# AB_ESP8266.net
KiCad netlist of a schematic drawn in EAGLE
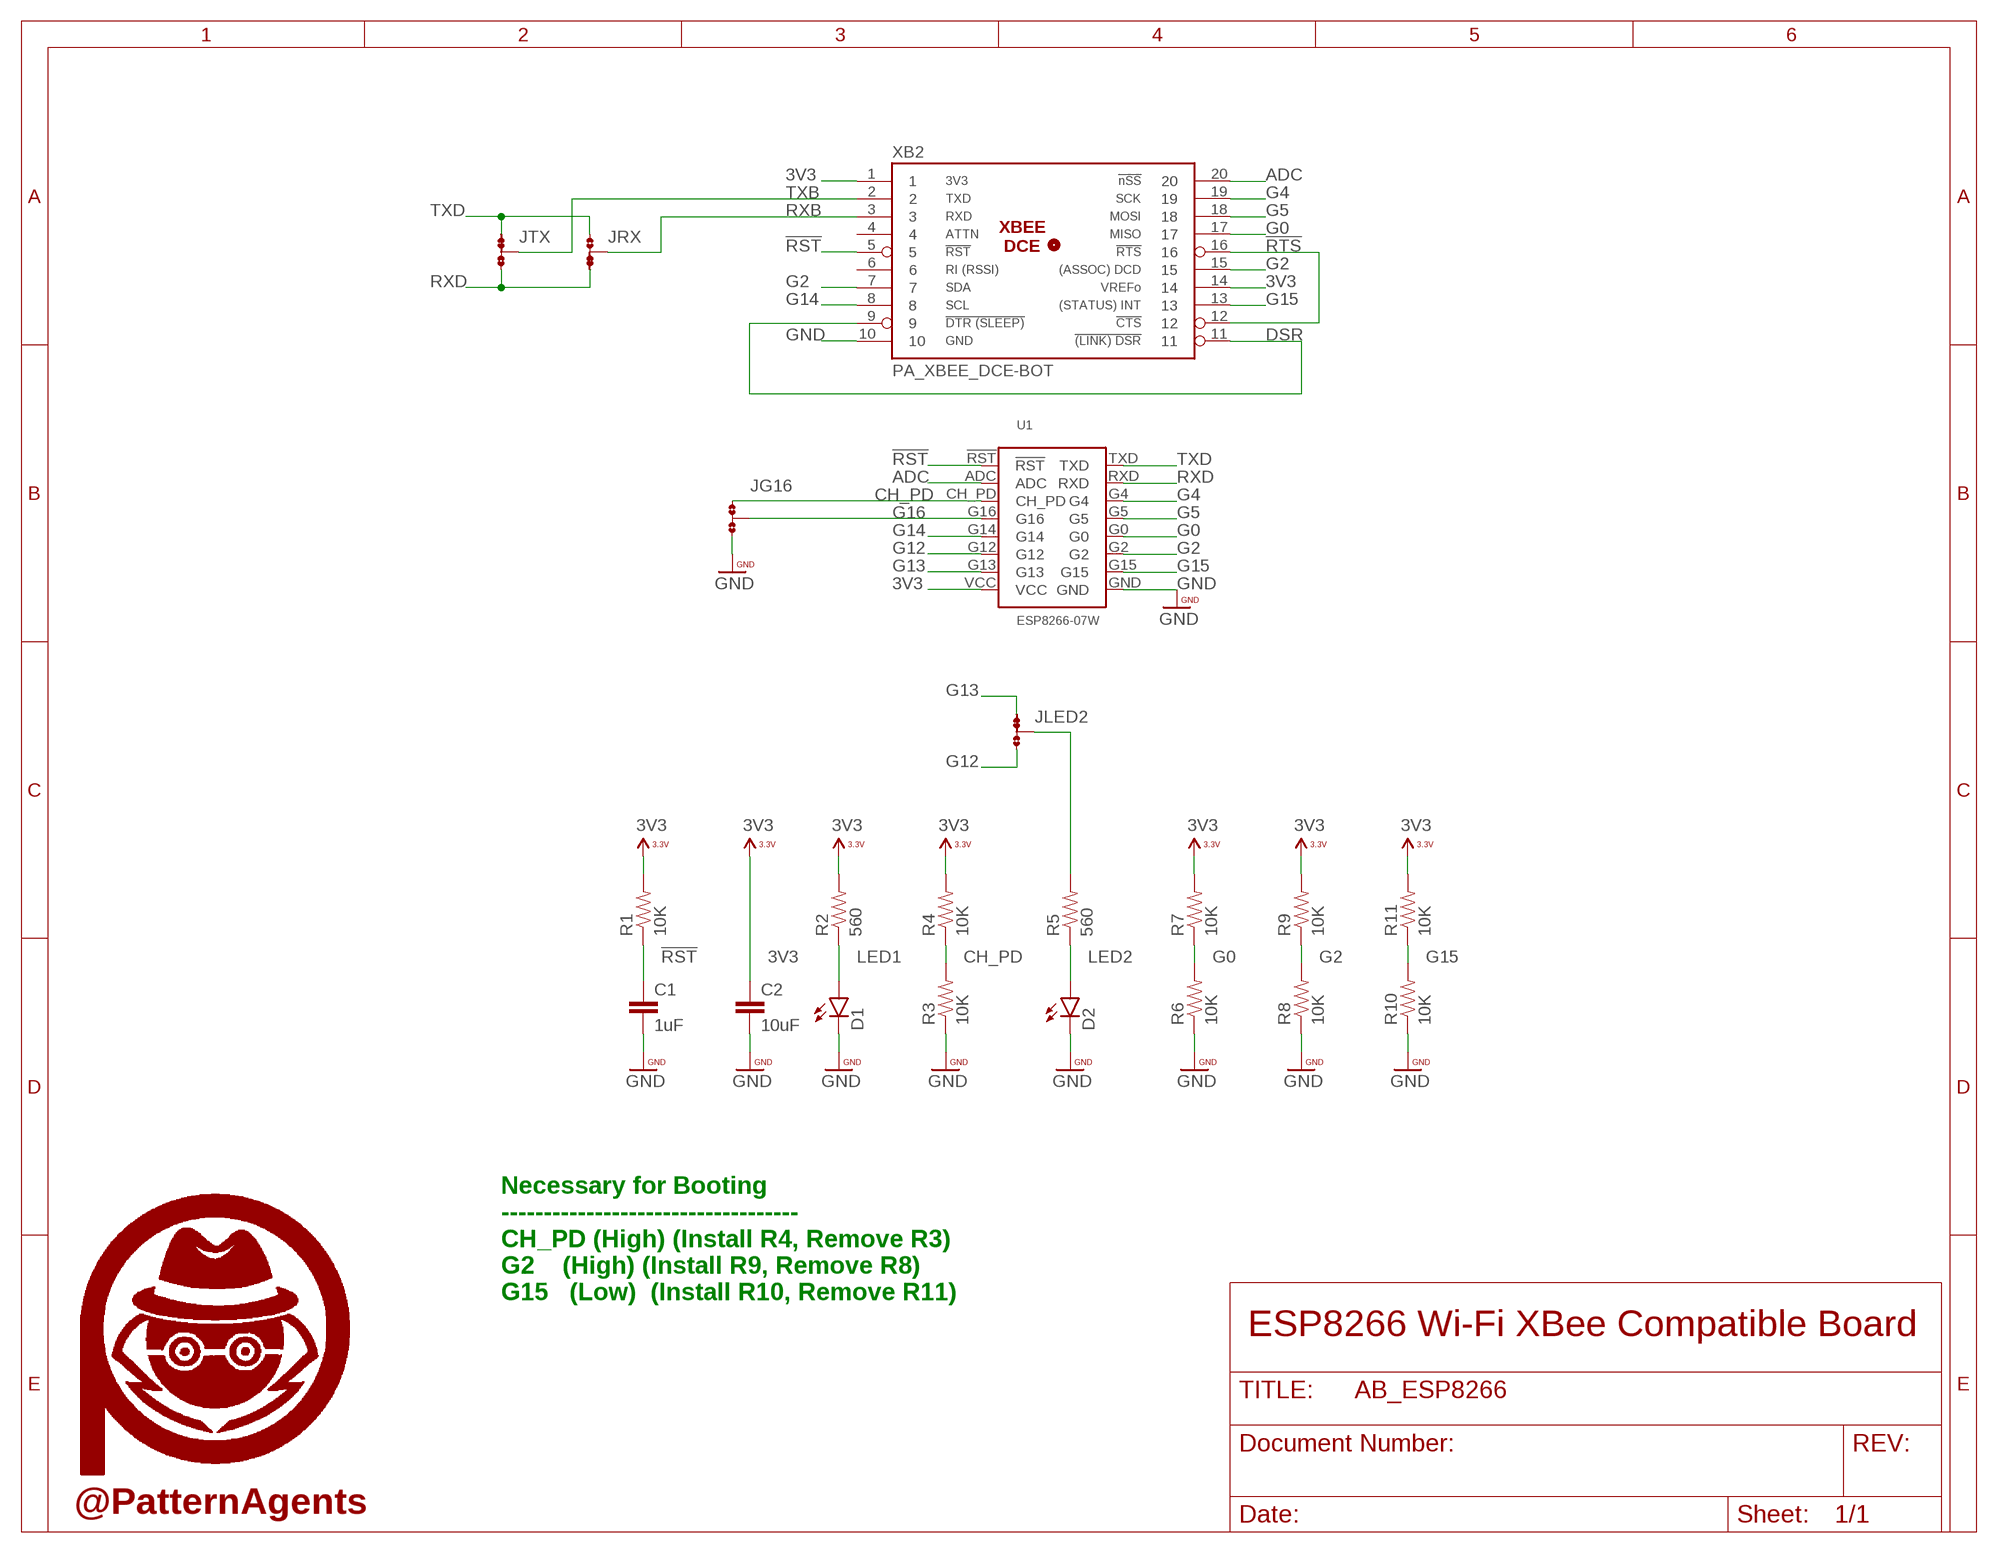
[diagram p0: schematic, sheet 1]

(export (version "E")
  (design (tool "Eeschema 10.0.6"))
  (components
    (comp (ref "C1")
      (value "1uF")
      (footprint "eagle-import:0603-CAP")
      (libsource (lib "eagle-import") (part "CAP0603-CAP"))
    )
    (comp (ref "C2")
      (value "10uF")
      (footprint "eagle-import:0603-CAP")
      (libsource (lib "eagle-import") (part "CAP0603-CAP"))
    )
    (comp (ref "D1")
      (value "LED0603")
      (footprint "eagle-import:LED-0603")
      (libsource (lib "eagle-import") (part "LED0603"))
    )
    (comp (ref "D2")
      (value "LED0603")
      (footprint "eagle-import:LED-0603")
      (libsource (lib "eagle-import") (part "LED0603"))
    )
    (comp (ref "JG16")
      (value "JMP-3-NO")
      (footprint "eagle-import:JMP-3-NO")
      (libsource (lib "eagle-import") (part "JMP-3-NO"))
    )
    (comp (ref "JLED2")
      (value "JMP-3-1_2")
      (footprint "eagle-import:JMP-3-1_2")
      (libsource (lib "eagle-import") (part "JMP-3-1_2"))
    )
    (comp (ref "JRX")
      (value "JMP-3-2_3")
      (footprint "eagle-import:JMP-3-2_3")
      (libsource (lib "eagle-import") (part "JMP-3-2_3"))
    )
    (comp (ref "JTX")
      (value "JMP-3-1_2")
      (footprint "eagle-import:JMP-3-1_2")
      (libsource (lib "eagle-import") (part "JMP-3-1_2"))
    )
    (comp (ref "R1")
      (value "10K")
      (footprint "eagle-import:0603-RES")
      (libsource (lib "eagle-import") (part "RESISTOR_SFE0603-RES"))
    )
    (comp (ref "R2")
      (value "560")
      (footprint "eagle-import:0603-RES")
      (libsource (lib "eagle-import") (part "RESISTOR_SFE0603-RES"))
    )
    (comp (ref "R3")
      (value "10K")
      (footprint "eagle-import:0603-RES")
      (libsource (lib "eagle-import") (part "RESISTOR_SFE0603-RES"))
    )
    (comp (ref "R4")
      (value "10K")
      (footprint "eagle-import:0603-RES")
      (libsource (lib "eagle-import") (part "RESISTOR_SFE0603-RES"))
    )
    (comp (ref "R5")
      (value "560")
      (footprint "eagle-import:0603-RES")
      (libsource (lib "eagle-import") (part "RESISTOR_SFE0603-RES"))
    )
    (comp (ref "R6")
      (value "10K")
      (footprint "eagle-import:0603-RES")
      (libsource (lib "eagle-import") (part "RESISTOR_SFE0603-RES"))
    )
    (comp (ref "R7")
      (value "10K")
      (footprint "eagle-import:0603-RES")
      (libsource (lib "eagle-import") (part "RESISTOR_SFE0603-RES"))
    )
    (comp (ref "R8")
      (value "10K")
      (footprint "eagle-import:0603-RES")
      (libsource (lib "eagle-import") (part "RESISTOR_SFE0603-RES"))
    )
    (comp (ref "R9")
      (value "10K")
      (footprint "eagle-import:0603-RES")
      (libsource (lib "eagle-import") (part "RESISTOR_SFE0603-RES"))
    )
    (comp (ref "R10")
      (value "10K")
      (footprint "eagle-import:0603-RES")
      (libsource (lib "eagle-import") (part "RESISTOR_SFE0603-RES"))
    )
    (comp (ref "R11")
      (value "10K")
      (footprint "eagle-import:0603-RES")
      (libsource (lib "eagle-import") (part "RESISTOR_SFE0603-RES"))
    )
    (comp (ref "U$18")
      (value "PA_LOGO_SYMSMALL")
      (footprint "eagle-import:PA_LOGO_AGENT_SMALL_SYM")
      (libsource (lib "eagle-import") (part "PA_LOGO_SYMSMALL"))
    )
    (comp (ref "U$19")
      (value "PA_LOGO_SYMSMALL")
      (footprint "eagle-import:PA_LOGO_AGENT_SMALL_SYM")
      (libsource (lib "eagle-import") (part "PA_LOGO_SYMSMALL"))
    )
    (comp (ref "U1")
      (value "ESP8266-07W")
      (footprint "eagle-import:ESP8266-07W")
      (libsource (lib "eagle-import") (part "ESP8266-07W"))
    )
    (comp (ref "XB2")
      (value "PA_XBEE_DCE-BOT")
      (footprint "eagle-import:PA_XBEE_SMD_BOT")
      (libsource (lib "eagle-import") (part "PA_XBEE_DCE-BOT"))
    )
  )
  (nets
    (net (code "1") (name "/ADC") (class "Default")
      (node (ref "U1") (pin "ADC") (pinfunction "ADC_ADC") (pintype "bidirectional"))
      (node (ref "XB2") (pin "20") (pinfunction "20_20") (pintype "input"))
    )
    (net (code "2") (name "/CH_PD") (class "Default")
      (node (ref "JG16") (pin "1") (pinfunction "1_1") (pintype "passive"))
      (node (ref "R3") (pin "2") (pinfunction "2_2") (pintype "passive"))
      (node (ref "R4") (pin "1") (pinfunction "1_1") (pintype "passive"))
      (node (ref "U1") (pin "CH_PD") (pinfunction "CH_PD_CH_PD") (pintype "bidirectional"))
    )
    (net (code "3") (name "/DSR") (class "Default")
      (node (ref "XB2") (pin "11") (pinfunction "11_11") (pintype "output"))
      (node (ref "XB2") (pin "9") (pinfunction "9_9") (pintype "input"))
    )
    (net (code "4") (name "/G0") (class "Default")
      (node (ref "R6") (pin "2") (pinfunction "2_2") (pintype "passive"))
      (node (ref "R7") (pin "1") (pinfunction "1_1") (pintype "passive"))
      (node (ref "U1") (pin "G0") (pinfunction "G0_G0") (pintype "bidirectional"))
      (node (ref "XB2") (pin "17") (pinfunction "17_17") (pintype "output"))
    )
    (net (code "5") (name "/G2") (class "Default")
      (node (ref "R8") (pin "2") (pinfunction "2_2") (pintype "passive"))
      (node (ref "R9") (pin "1") (pinfunction "1_1") (pintype "passive"))
      (node (ref "U1") (pin "G2") (pinfunction "G2_G2") (pintype "bidirectional"))
      (node (ref "XB2") (pin "15") (pinfunction "15_15") (pintype "output"))
      (node (ref "XB2") (pin "7") (pinfunction "7_7") (pintype "bidirectional"))
    )
    (net (code "6") (name "/G4") (class "Default")
      (node (ref "U1") (pin "G4") (pinfunction "G4_G4") (pintype "bidirectional"))
      (node (ref "XB2") (pin "19") (pinfunction "19_19") (pintype "input"))
    )
    (net (code "7") (name "/G5") (class "Default")
      (node (ref "U1") (pin "G5") (pinfunction "G5_G5") (pintype "bidirectional"))
      (node (ref "XB2") (pin "18") (pinfunction "18_18") (pintype "input"))
    )
    (net (code "8") (name "/G12") (class "Default")
      (node (ref "JLED2") (pin "3") (pinfunction "3_3") (pintype "passive"))
      (node (ref "U1") (pin "G12") (pinfunction "G12_G12") (pintype "bidirectional"))
    )
    (net (code "9") (name "/G13") (class "Default")
      (node (ref "JLED2") (pin "1") (pinfunction "1_1") (pintype "passive"))
      (node (ref "U1") (pin "G13") (pinfunction "G13_G13") (pintype "bidirectional"))
    )
    (net (code "10") (name "/G14") (class "Default")
      (node (ref "U1") (pin "G14") (pinfunction "G14_G14") (pintype "bidirectional"))
      (node (ref "XB2") (pin "8") (pinfunction "8_8") (pintype "bidirectional"))
    )
    (net (code "11") (name "/G15") (class "Default")
      (node (ref "R10") (pin "2") (pinfunction "2_2") (pintype "passive"))
      (node (ref "R11") (pin "1") (pinfunction "1_1") (pintype "passive"))
      (node (ref "U1") (pin "G15") (pinfunction "G15_G15") (pintype "bidirectional"))
      (node (ref "XB2") (pin "13") (pinfunction "13_13") (pintype "output"))
    )
    (net (code "12") (name "/G16") (class "Default")
      (node (ref "JG16") (pin "2") (pinfunction "2_2") (pintype "passive"))
      (node (ref "U1") (pin "G16") (pinfunction "G16_G16") (pintype "bidirectional"))
    )
    (net (code "13") (name "/LED1") (class "Default")
      (node (ref "D1") (pin "A") (pinfunction "A_A") (pintype "passive"))
      (node (ref "R2") (pin "1") (pinfunction "1_1") (pintype "passive"))
    )
    (net (code "14") (name "/LED2") (class "Default")
      (node (ref "D2") (pin "A") (pinfunction "A_A") (pintype "passive"))
      (node (ref "R5") (pin "1") (pinfunction "1_1") (pintype "passive"))
    )
    (net (code "15") (name "/RXB") (class "Default")
      (node (ref "JRX") (pin "2") (pinfunction "2_2") (pintype "passive"))
      (node (ref "XB2") (pin "3") (pinfunction "3_3") (pintype "input"))
    )
    (net (code "16") (name "/RXD") (class "Default")
      (node (ref "JRX") (pin "3") (pinfunction "3_3") (pintype "passive"))
      (node (ref "JTX") (pin "3") (pinfunction "3_3") (pintype "passive"))
      (node (ref "U1") (pin "RXD") (pinfunction "RXD_RXD") (pintype "bidirectional"))
    )
    (net (code "17") (name "/TXB") (class "Default")
      (node (ref "JTX") (pin "2") (pinfunction "2_2") (pintype "passive"))
      (node (ref "XB2") (pin "2") (pinfunction "2_2") (pintype "input"))
    )
    (net (code "18") (name "/TXD") (class "Default")
      (node (ref "JRX") (pin "1") (pinfunction "1_1") (pintype "passive"))
      (node (ref "JTX") (pin "1") (pinfunction "1_1") (pintype "passive"))
      (node (ref "U1") (pin "TXD") (pinfunction "TXD_TXD") (pintype "bidirectional"))
    )
    (net (code "19") (name "/~{RST}") (class "Default")
      (node (ref "C1") (pin "1") (pinfunction "1_1") (pintype "passive"))
      (node (ref "R1") (pin "1") (pinfunction "1_1") (pintype "passive"))
      (node (ref "U1") (pin "!RST") (pinfunction "~{RST}_!RST") (pintype "bidirectional"))
      (node (ref "XB2") (pin "5") (pinfunction "5_5") (pintype "open_collector"))
    )
    (net (code "20") (name "/~{RTS}") (class "Default")
      (node (ref "XB2") (pin "12") (pinfunction "12_12") (pintype "output"))
      (node (ref "XB2") (pin "16") (pinfunction "16_16") (pintype "input"))
    )
    (net (code "21") (name "3V3") (class "Default")
      (node (ref "C2") (pin "1") (pinfunction "1_1") (pintype "passive"))
      (node (ref "R1") (pin "2") (pinfunction "2_2") (pintype "passive"))
      (node (ref "R11") (pin "2") (pinfunction "2_2") (pintype "passive"))
      (node (ref "R2") (pin "2") (pinfunction "2_2") (pintype "passive"))
      (node (ref "R4") (pin "2") (pinfunction "2_2") (pintype "passive"))
      (node (ref "R7") (pin "2") (pinfunction "2_2") (pintype "passive"))
      (node (ref "R9") (pin "2") (pinfunction "2_2") (pintype "passive"))
      (node (ref "U1") (pin "VCC") (pinfunction "VCC_VCC") (pintype "bidirectional"))
      (node (ref "XB2") (pin "1") (pinfunction "1_1") (pintype "power_in"))
      (node (ref "XB2") (pin "14") (pinfunction "14_14") (pintype "output"))
    )
    (net (code "22") (name "GND") (class "Default")
      (node (ref "C1") (pin "2") (pinfunction "2_2") (pintype "passive"))
      (node (ref "C2") (pin "2") (pinfunction "2_2") (pintype "passive"))
      (node (ref "D1") (pin "C") (pinfunction "C_C") (pintype "passive"))
      (node (ref "D2") (pin "C") (pinfunction "C_C") (pintype "passive"))
      (node (ref "JG16") (pin "3") (pinfunction "3_3") (pintype "passive"))
      (node (ref "R10") (pin "1") (pinfunction "1_1") (pintype "passive"))
      (node (ref "R3") (pin "1") (pinfunction "1_1") (pintype "passive"))
      (node (ref "R6") (pin "1") (pinfunction "1_1") (pintype "passive"))
      (node (ref "R8") (pin "1") (pinfunction "1_1") (pintype "passive"))
      (node (ref "U1") (pin "GND") (pinfunction "GND_GND") (pintype "bidirectional"))
      (node (ref "XB2") (pin "10") (pinfunction "10_10") (pintype "power_in"))
    )
    (net (code "23") (name "Net-(JLED2-Pad2)") (class "Default")
      (node (ref "JLED2") (pin "2") (pinfunction "2_2") (pintype "passive"))
      (node (ref "R5") (pin "2") (pinfunction "2_2") (pintype "passive"))
    )
    (net (code "24") (name "unconnected-(XB2-Pad4)") (class "Default")
      (node (ref "XB2") (pin "4") (pinfunction "4_4") (pintype "bidirectional"))
    )
    (net (code "25") (name "unconnected-(XB2-Pad6)") (class "Default")
      (node (ref "XB2") (pin "6") (pinfunction "6_6") (pintype "output"))
    )
  )
)
